# HeroRobot.net
KiCad netlist of a schematic drawn in Altium Designer
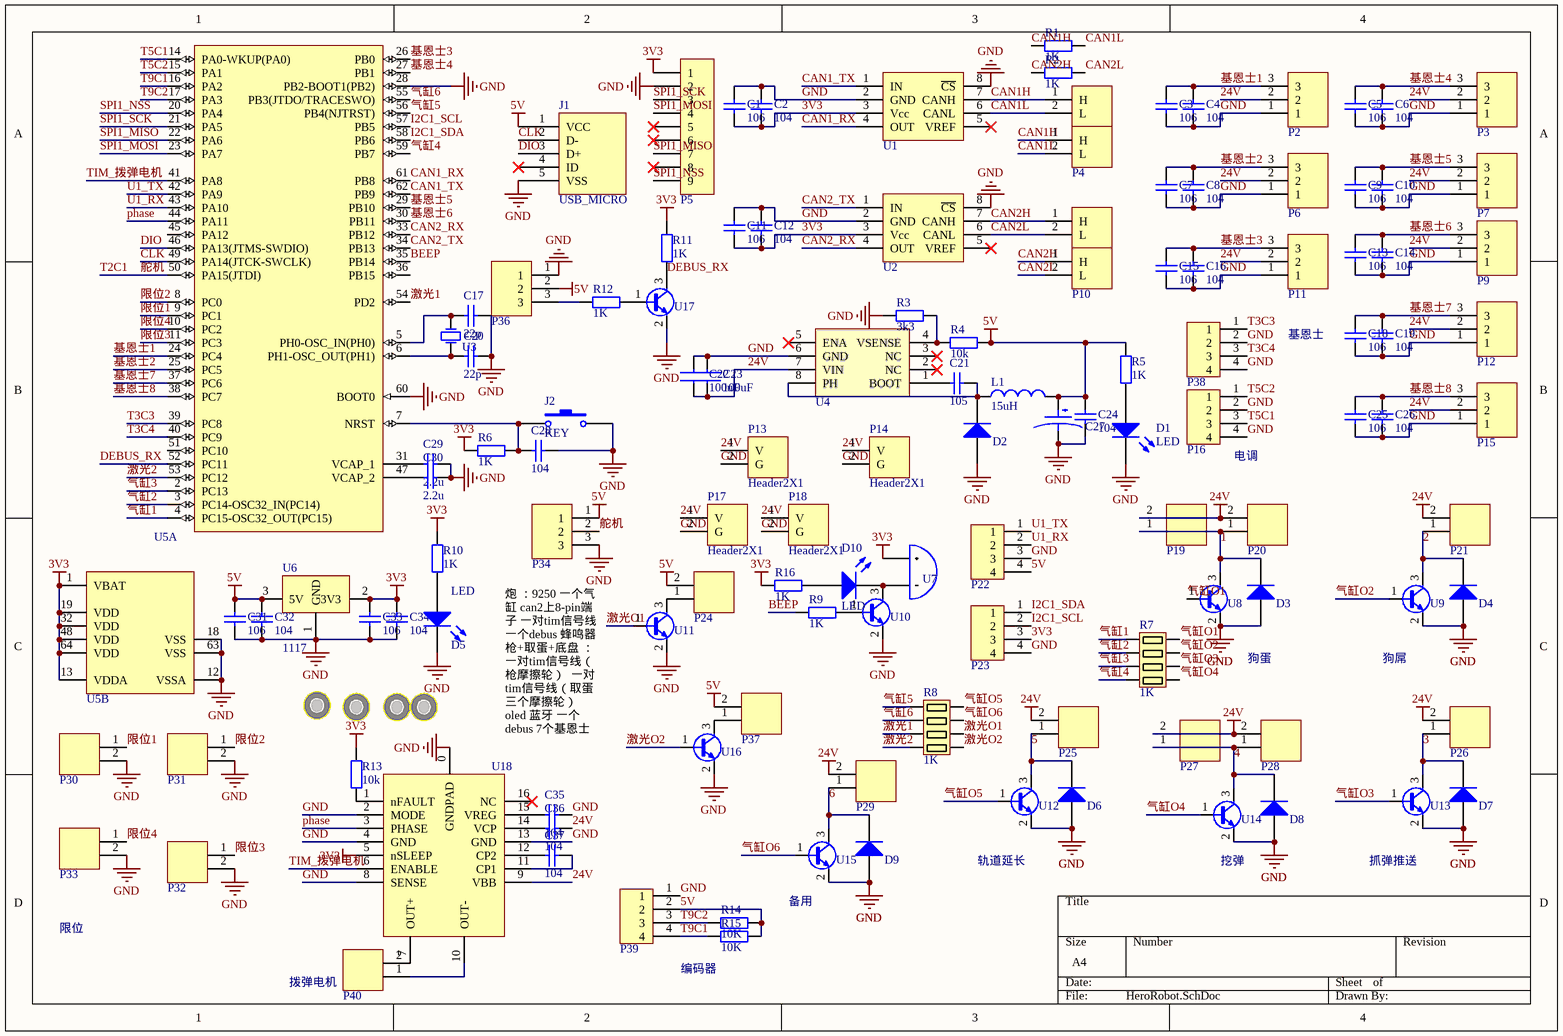
[diagram p0: HeroRobot.SchDoc]

(export (version "E")
  (design (tool "Eeschema 10.0.6"))
  (components
    (comp (ref "1") (value "Via_M3") (footprint "Via_M3") (libsource (lib "SHAWN") (part "Via_M3")))
    (comp (ref "2") (value "Via_M3") (footprint "Via_M3") (libsource (lib "SHAWN") (part "Via_M3")))
    (comp (ref "3") (value "Via_M3") (footprint "Via_M3") (libsource (lib "SHAWN") (part "Via_M3")))
    (comp (ref "4") (value "Via_M3") (footprint "Via_M3") (libsource (lib "SHAWN") (part "Via_M3")))
    (comp (ref "C1")
      (value "106")
      (footprint "0603C")
      (description "0603/0805")
      (libsource (lib "SHAWN") (part "C_106"))
    )
    (comp (ref "C2")
      (value "104")
      (footprint "0603C")
      (description "0603/0805")
      (libsource (lib "SHAWN") (part "C_104"))
    )
    (comp (ref "C3")
      (value "106")
      (footprint "0603C")
      (description "0603/0805")
      (libsource (lib "SHAWN") (part "C_106"))
    )
    (comp (ref "C4")
      (value "104")
      (footprint "0603C")
      (description "0603/0805")
      (libsource (lib "SHAWN") (part "C_104"))
    )
    (comp (ref "C5")
      (value "106")
      (footprint "0603C")
      (description "0603/0805")
      (libsource (lib "SHAWN") (part "C_106"))
    )
    (comp (ref "C6")
      (value "104")
      (footprint "0603C")
      (description "0603/0805")
      (libsource (lib "SHAWN") (part "C_104"))
    )
    (comp (ref "C7")
      (value "106")
      (footprint "0603C")
      (description "0603/0805")
      (libsource (lib "SHAWN") (part "C_106"))
    )
    (comp (ref "C8")
      (value "104")
      (footprint "0603C")
      (description "0603/0805")
      (libsource (lib "SHAWN") (part "C_104"))
    )
    (comp (ref "C9")
      (value "106")
      (footprint "0603C")
      (description "0603/0805")
      (libsource (lib "SHAWN") (part "C_106"))
    )
    (comp (ref "C10")
      (value "104")
      (footprint "0603C")
      (description "0603/0805")
      (libsource (lib "SHAWN") (part "C_104"))
    )
    (comp (ref "C11")
      (value "106")
      (footprint "0603C")
      (description "0603/0805")
      (libsource (lib "SHAWN") (part "C_106"))
    )
    (comp (ref "C12")
      (value "104")
      (footprint "0603C")
      (description "0603/0805")
      (libsource (lib "SHAWN") (part "C_104"))
    )
    (comp (ref "C13")
      (value "106")
      (footprint "0603C")
      (description "0603/0805")
      (libsource (lib "SHAWN") (part "C_106"))
    )
    (comp (ref "C14")
      (value "104")
      (footprint "0603C")
      (description "0603/0805")
      (libsource (lib "SHAWN") (part "C_104"))
    )
    (comp (ref "C15")
      (value "106")
      (footprint "0603C")
      (description "0603/0805")
      (libsource (lib "SHAWN") (part "C_106"))
    )
    (comp (ref "C16")
      (value "104")
      (footprint "0603C")
      (description "0603/0805")
      (libsource (lib "SHAWN") (part "C_104"))
    )
    (comp (ref "C17")
      (value "22p")
      (footprint "0603C")
      (description "0603/0805")
      (libsource (lib "SHAWN") (part "C_104"))
    )
    (comp (ref "C18")
      (value "106")
      (footprint "0603C")
      (description "0603/0805")
      (libsource (lib "SHAWN") (part "C_106"))
    )
    (comp (ref "C19")
      (value "104")
      (footprint "0603C")
      (description "0603/0805")
      (libsource (lib "SHAWN") (part "C_104"))
    )
    (comp (ref "C20")
      (value "22p")
      (footprint "0603C")
      (description "0603/0805")
      (libsource (lib "SHAWN") (part "C_104"))
    )
    (comp (ref "C21")
      (value "105")
      (footprint "0603C")
      (description "0603/0805")
      (libsource (lib "SHAWN") (part "C_106"))
    )
    (comp (ref "C22") (value "100uF") (footprint "1201C") (libsource (lib "SHAWN") (part "CAP100uF")))
    (comp (ref "C23") (value "100uF") (footprint "1201C") (libsource (lib "SHAWN") (part "CAP100uF")))
    (comp (ref "C24")
      (value "104")
      (footprint "0603C")
      (description "0603/0805")
      (libsource (lib "SHAWN") (part "C_104"))
    )
    (comp (ref "C25")
      (value "106")
      (footprint "0603C")
      (description "0603/0805")
      (libsource (lib "SHAWN") (part "C_106"))
    )
    (comp (ref "C26")
      (value "104")
      (footprint "0603C")
      (description "0603/0805")
      (libsource (lib "SHAWN") (part "C_104"))
    )
    (comp (ref "C27")
      (value "CAP_钽220")
      (footprint "cap_钽E封装")
      (description "CAP")
      (libsource (lib "SHAWN") (part "CAP_钽220"))
    )
    (comp (ref "C28")
      (value "104")
      (footprint "0603C")
      (description "0603/0805")
      (libsource (lib "SHAWN") (part "C_104"))
    )
    (comp (ref "C29")
      (value "2.2u")
      (footprint "0603C")
      (description "0603/0805")
      (libsource (lib "SHAWN") (part "C_104"))
    )
    (comp (ref "C30")
      (value "2.2u")
      (footprint "0603C")
      (description "0603/0805")
      (libsource (lib "SHAWN") (part "C_104"))
    )
    (comp (ref "C31")
      (value "106")
      (footprint "0603C")
      (description "0603/0805")
      (libsource (lib "SHAWN") (part "C_106"))
    )
    (comp (ref "C32")
      (value "104")
      (footprint "0603C")
      (description "0603/0805")
      (libsource (lib "SHAWN") (part "C_104"))
    )
    (comp (ref "C33")
      (value "106")
      (footprint "0603C")
      (description "0603/0805")
      (libsource (lib "SHAWN") (part "C_106"))
    )
    (comp (ref "C34")
      (value "104")
      (footprint "0603C")
      (description "0603/0805")
      (libsource (lib "SHAWN") (part "C_104"))
    )
    (comp (ref "C35")
      (value "104")
      (footprint "0603C")
      (description "0603/0805")
      (libsource (lib "SHAWN") (part "C_104"))
    )
    (comp (ref "C36")
      (value "104")
      (footprint "0603C")
      (description "0603/0805")
      (libsource (lib "SHAWN") (part "C_104"))
    )
    (comp (ref "C37")
      (value "104")
      (footprint "0603C")
      (description "0603/0805")
      (libsource (lib "SHAWN") (part "C_104"))
    )
    (comp (ref "D1") (value "LED") (footprint "LED_0603") (libsource (lib "SHAWN") (part "LED")))
    (comp (ref "D2")
      (value "Diode_SS34")
      (footprint "Diode_SS34")
      (description "肖特基二极管")
      (libsource (lib "SHAWN") (part "Diode_SS34"))
    )
    (comp (ref "D3")
      (value "Diode_SS34")
      (footprint "Diode_SS34")
      (description "肖特基二极管")
      (libsource (lib "SHAWN") (part "Diode_SS34"))
    )
    (comp (ref "D4")
      (value "Diode_SS34")
      (footprint "Diode_SS34")
      (description "肖特基二极管")
      (libsource (lib "SHAWN") (part "Diode_SS34"))
    )
    (comp (ref "D5") (value "LED") (footprint "LED_0603") (libsource (lib "SHAWN") (part "LED")))
    (comp (ref "D6")
      (value "Diode_SS34")
      (footprint "Diode_SS34")
      (description "肖特基二极管")
      (libsource (lib "SHAWN") (part "Diode_SS34"))
    )
    (comp (ref "D7")
      (value "Diode_SS34")
      (footprint "Diode_SS34")
      (description "肖特基二极管")
      (libsource (lib "SHAWN") (part "Diode_SS34"))
    )
    (comp (ref "D8")
      (value "Diode_SS34")
      (footprint "Diode_SS34")
      (description "肖特基二极管")
      (libsource (lib "SHAWN") (part "Diode_SS34"))
    )
    (comp (ref "D9")
      (value "Diode_SS34")
      (footprint "Diode_SS34")
      (description "肖特基二极管")
      (libsource (lib "SHAWN") (part "Diode_SS34"))
    )
    (comp (ref "D10") (value "LED") (footprint "LED_0603") (libsource (lib "SHAWN") (part "LED")))
    (comp (ref "J1") (value "USB_MICRO") (footprint "USB_MICRO") (libsource (lib "SHAWN") (part "USB_MICRO")))
    (comp (ref "J2") (value "KEY") (footprint "KEY") (libsource (lib "SHAWN") (part "KEY")))
    (comp (ref "L1")
      (value "15uH")
      (footprint "Inductor7.2X7.2")
      (description "屏蔽电感")
      (libsource (lib "SHAWN") (part "Inductor"))
    )
    (comp (ref "P1")
      (value "Header_CAN")
      (footprint "Header2_3002")
      (libsource (lib "SHAWN") (part "Header_CAN"))
    )
    (comp (ref "P2") (value "Header3") (footprint "Header3_white") (libsource (lib "SHAWN") (part "Header3")))
    (comp (ref "P3") (value "Header3") (footprint "Header3_white") (libsource (lib "SHAWN") (part "Header3")))
    (comp (ref "P4")
      (value "Header_CAN")
      (footprint "Header2_3002")
      (libsource (lib "SHAWN") (part "Header_CAN"))
    )
    (comp (ref "P5") (value "Header9") (footprint "Header9") (libsource (lib "SHAWN") (part "Header9")))
    (comp (ref "P6") (value "Header3") (footprint "Header3_white") (libsource (lib "SHAWN") (part "Header3")))
    (comp (ref "P7") (value "Header3") (footprint "Header3_white") (libsource (lib "SHAWN") (part "Header3")))
    (comp (ref "P8")
      (value "Header_CAN")
      (footprint "Header2_3002")
      (libsource (lib "SHAWN") (part "Header_CAN"))
    )
    (comp (ref "P9") (value "Header3") (footprint "Header3_white") (libsource (lib "SHAWN") (part "Header3")))
    (comp (ref "P10")
      (value "Header_CAN")
      (footprint "Header2_3002")
      (libsource (lib "SHAWN") (part "Header_CAN"))
    )
    (comp (ref "P11")
      (value "Header3")
      (footprint "Header3_white")
      (libsource (lib "SHAWN") (part "Header3"))
    )
    (comp (ref "P12")
      (value "Header3")
      (footprint "Header3_white")
      (libsource (lib "SHAWN") (part "Header3"))
    )
    (comp (ref "P13")
      (value "Header2X1")
      (footprint "Header_POWER")
      (description "power")
      (libsource (lib "SHAWN") (part "Header2X1"))
    )
    (comp (ref "P14")
      (value "Header2X1")
      (footprint "Header_POWER")
      (description "power")
      (libsource (lib "SHAWN") (part "Header2X1"))
    )
    (comp (ref "P15")
      (value "Header3")
      (footprint "Header3_white")
      (libsource (lib "SHAWN") (part "Header3"))
    )
    (comp (ref "P16")
      (value "Header4")
      (footprint "Header4_white")
      (libsource (lib "SHAWN") (part "Header4"))
    )
    (comp (ref "P17")
      (value "Header2X1")
      (footprint "Header_POWER")
      (description "power")
      (libsource (lib "SHAWN") (part "Header2X1"))
    )
    (comp (ref "P18")
      (value "Header2X1")
      (footprint "Header_POWER")
      (description "power")
      (libsource (lib "SHAWN") (part "Header2X1"))
    )
    (comp (ref "P19") (value "Header") (footprint "Header2_white") (libsource (lib "SHAWN") (part "Header2")))
    (comp (ref "P20") (value "Header") (footprint "Header2_white") (libsource (lib "SHAWN") (part "Header2")))
    (comp (ref "P21") (value "Header") (footprint "Header2_white") (libsource (lib "SHAWN") (part "Header2")))
    (comp (ref "P22") (value "Header4") (footprint "Header4") (libsource (lib "SHAWN") (part "Header4")))
    (comp (ref "P23") (value "Header4") (footprint "Header4") (libsource (lib "SHAWN") (part "Header4")))
    (comp (ref "P24") (value "Header") (footprint "Header2_white") (libsource (lib "SHAWN") (part "Header2")))
    (comp (ref "P25") (value "Header") (footprint "Header2_white") (libsource (lib "SHAWN") (part "Header2")))
    (comp (ref "P26") (value "Header") (footprint "Header2_white") (libsource (lib "SHAWN") (part "Header2")))
    (comp (ref "P27") (value "Header") (footprint "Header2_white") (libsource (lib "SHAWN") (part "Header2")))
    (comp (ref "P28") (value "Header") (footprint "Header2_white") (libsource (lib "SHAWN") (part "Header2")))
    (comp (ref "P29") (value "Header") (footprint "Header2_white") (libsource (lib "SHAWN") (part "Header2")))
    (comp (ref "P30") (value "Header") (footprint "Header2_white") (libsource (lib "") (part "Header2_2")))
    (comp (ref "P31") (value "Header") (footprint "Header2_white") (libsource (lib "") (part "Header2_2")))
    (comp (ref "P32") (value "Header") (footprint "Header2_white") (libsource (lib "") (part "Header2_2")))
    (comp (ref "P33") (value "Header") (footprint "Header2_white") (libsource (lib "") (part "Header2_2")))
    (comp (ref "P34") (value "Header3") (footprint "Header3_white") (libsource (lib "") (part "Header3_1")))
    (comp (ref "P36") (value "Header3") (footprint "Header3_white") (libsource (lib "") (part "Header3_1")))
    (comp (ref "P37") (value "Header") (footprint "Header2_white") (libsource (lib "SHAWN") (part "Header2")))
    (comp (ref "P38")
      (value "Header4")
      (footprint "Header4_white")
      (libsource (lib "SHAWN") (part "Header4"))
    )
    (comp (ref "P39")
      (value "Header4")
      (footprint "Header4_white")
      (libsource (lib "SHAWN") (part "Header4"))
    )
    (comp (ref "P40") (value "Header") (footprint "Header2_white") (libsource (lib "") (part "Header2_1")))
    (comp (ref "R1")
      (value "1K")
      (footprint "0603R")
      (description "0603/0805")
      (libsource (lib "SHAWN") (part "R"))
    )
    (comp (ref "R2")
      (value "1K")
      (footprint "0603R")
      (description "0603/0805")
      (libsource (lib "SHAWN") (part "R"))
    )
    (comp (ref "R3")
      (value "3k3")
      (footprint "0603R")
      (description "0603/0805")
      (libsource (lib "") (part "R_2"))
    )
    (comp (ref "R4")
      (value "10k")
      (footprint "0603R")
      (description "0603/0805")
      (libsource (lib "") (part "R_2"))
    )
    (comp (ref "R5")
      (value "1K")
      (footprint "0603R")
      (description "0603/0805")
      (libsource (lib "") (part "R_1"))
    )
    (comp (ref "R6")
      (value "1K")
      (footprint "0603R")
      (description "0603/0805")
      (libsource (lib "") (part "R_2"))
    )
    (comp (ref "R7") (value "1K") (footprint "8P4R_0603") (libsource (lib "SHAWN") (part "R_8P4R")))
    (comp (ref "R8") (value "1K") (footprint "8P4R_0603") (libsource (lib "SHAWN") (part "R_8P4R")))
    (comp (ref "R9")
      (value "1K")
      (footprint "0603R")
      (description "0603/0805")
      (libsource (lib "") (part "R_2"))
    )
    (comp (ref "R10")
      (value "1K")
      (footprint "0603R")
      (description "0603/0805")
      (libsource (lib "") (part "R_1"))
    )
    (comp (ref "R11")
      (value "1K")
      (footprint "0603R")
      (description "0603/0805")
      (libsource (lib "") (part "R_1"))
    )
    (comp (ref "R12")
      (value "1K")
      (footprint "0603R")
      (description "0603/0805")
      (libsource (lib "") (part "R_2"))
    )
    (comp (ref "R13")
      (value "10k")
      (footprint "0603R")
      (description "0603/0805")
      (libsource (lib "") (part "R_1"))
    )
    (comp (ref "R14")
      (value "10K")
      (footprint "0603R")
      (description "0603/0805")
      (libsource (lib "SHAWN") (part "R"))
    )
    (comp (ref "R15")
      (value "10K")
      (footprint "0603R")
      (description "0603/0805")
      (libsource (lib "SHAWN") (part "R"))
    )
    (comp (ref "R16")
      (value "1K")
      (footprint "0603R")
      (description "0603/0805")
      (libsource (lib "SHAWN") (part "R"))
    )
    (comp (ref "U1")
      (value "VD230")
      (footprint "SO_8")
      (description "SO-8")
      (libsource (lib "SHAWN") (part "VD230"))
    )
    (comp (ref "U2")
      (value "VD230")
      (footprint "SO_8")
      (description "SO-8")
      (libsource (lib "SHAWN") (part "VD230"))
    )
    (comp (ref "U3") (value "XTAL") (footprint "XATL_8M") (libsource (lib "SHAWN") (part "XTAL")))
    (comp (ref "U4")
      (value "TPS5430/5450")
      (footprint "TPS5430")
      (description "降压")
      (libsource (lib "SHAWN") (part "TPS5430/5450"))
    )
    (comp (ref "U5")
      (value "STM32F405RGT6(F103RCT6)")
      (footprint "LQFP_64Pins - duplicate")
      (description "64PINS")
      (libsource (lib "SHAWN") (part "STM32F405RGT6(F103RCT6)"))
    )
    (comp (ref "U6") (value "1117") (footprint "SOT-223") (libsource (lib "SHAWN") (part "AMS1117-3.3")))
    (comp (ref "U7") (value "Bell") (footprint "BELL_无源") (libsource (lib "SHAWN") (part "Bell")))
    (comp (ref "U8") (value "BJT-2N5551") (footprint "SOT_23") (libsource (lib "SHAWN") (part "BJT-2N5551")))
    (comp (ref "U9") (value "BJT-2N5551") (footprint "SOT_23") (libsource (lib "SHAWN") (part "BJT-2N5551")))
    (comp (ref "U10") (value "BJT-2N5551") (footprint "SOT_23") (libsource (lib "SHAWN") (part "BJT-2N5551")))
    (comp (ref "U11") (value "BJT-2N5551") (footprint "SOT_23") (libsource (lib "SHAWN") (part "BJT-2N5551")))
    (comp (ref "U12") (value "BJT-2N5551") (footprint "SOT_23") (libsource (lib "SHAWN") (part "BJT-2N5551")))
    (comp (ref "U13") (value "BJT-2N5551") (footprint "SOT_23") (libsource (lib "SHAWN") (part "BJT-2N5551")))
    (comp (ref "U14") (value "BJT-2N5551") (footprint "SOT_23") (libsource (lib "SHAWN") (part "BJT-2N5551")))
    (comp (ref "U15") (value "BJT-2N5551") (footprint "SOT_23") (libsource (lib "SHAWN") (part "BJT-2N5551")))
    (comp (ref "U16") (value "BJT-2N5551") (footprint "SOT_23") (libsource (lib "SHAWN") (part "BJT-2N5551")))
    (comp (ref "U17") (value "BJT-2N5551") (footprint "SOT_23") (libsource (lib "SHAWN") (part "BJT-2N5551")))
    (comp (ref "U18")
      (value "DRV8800")
      (footprint "HTSSOP")
      (description "HTSSOP")
      (libsource (lib "SHAWN") (part "DRV8800"))
    )
  )
  (nets
    (net (code "1") (name "/1") (class "Default")
      (node (ref "D3") (pin "2") (pinfunction "K_2") (pintype "passive"))
      (node (ref "P19") (pin "1") (pinfunction "1_1") (pintype "passive"))
      (node (ref "P20") (pin "1") (pinfunction "1_1") (pintype "passive"))
      (node (ref "U8") (pin "3") (pinfunction "c_3") (pintype "passive"))
    )
    (net (code "2") (name "/2") (class "Default")
      (node (ref "D4") (pin "2") (pinfunction "K_2") (pintype "passive"))
      (node (ref "P21") (pin "1") (pinfunction "1_1") (pintype "passive"))
      (node (ref "U9") (pin "3") (pinfunction "c_3") (pintype "passive"))
    )
    (net (code "3") (name "/3") (class "Default")
      (node (ref "D7") (pin "2") (pinfunction "K_2") (pintype "passive"))
      (node (ref "P26") (pin "1") (pinfunction "1_1") (pintype "passive"))
      (node (ref "U13") (pin "3") (pinfunction "c_3") (pintype "passive"))
    )
    (net (code "4") (name "/4") (class "Default")
      (node (ref "D8") (pin "2") (pinfunction "K_2") (pintype "passive"))
      (node (ref "P27") (pin "1") (pinfunction "1_1") (pintype "passive"))
      (node (ref "P28") (pin "1") (pinfunction "1_1") (pintype "passive"))
      (node (ref "U14") (pin "3") (pinfunction "c_3") (pintype "passive"))
    )
    (net (code "5") (name "/5") (class "Default")
      (node (ref "D6") (pin "2") (pinfunction "K_2") (pintype "passive"))
      (node (ref "P25") (pin "1") (pinfunction "1_1") (pintype "passive"))
      (node (ref "U12") (pin "3") (pinfunction "c_3") (pintype "passive"))
    )
    (net (code "6") (name "/6") (class "Default")
      (node (ref "D9") (pin "2") (pinfunction "K_2") (pintype "passive"))
      (node (ref "P29") (pin "1") (pinfunction "1_1") (pintype "passive"))
      (node (ref "U15") (pin "3") (pinfunction "c_3") (pintype "passive"))
    )
    (net (code "7") (name "/BEEP") (class "Default")
      (node (ref "R9") (pin "2") (pinfunction "2_2") (pintype "passive"))
      (node (ref "U5") (pin "35") (pinfunction "PB14_35") (pintype "bidirectional"))
    )
    (net (code "8") (name "/CAN1H") (class "Default")
      (node (ref "P1") (pin "1") (pinfunction "H_1") (pintype "passive"))
      (node (ref "P4") (pin "1") (pinfunction "H_1") (pintype "passive"))
      (node (ref "R1") (pin "1") (pinfunction "1_1") (pintype "passive"))
      (node (ref "U1") (pin "7") (pinfunction "CANH_7") (pintype "passive"))
    )
    (net (code "9") (name "/CAN1L") (class "Default")
      (node (ref "P1") (pin "2") (pinfunction "L_2") (pintype "passive"))
      (node (ref "P4") (pin "2") (pinfunction "L_2") (pintype "passive"))
      (node (ref "R1") (pin "2") (pinfunction "2_2") (pintype "passive"))
      (node (ref "U1") (pin "6") (pinfunction "CANL_6") (pintype "passive"))
    )
    (net (code "10") (name "/CAN1_RX") (class "Default")
      (node (ref "U1") (pin "4") (pinfunction "OUT_4") (pintype "passive"))
      (node (ref "U5") (pin "61") (pinfunction "PB8_61") (pintype "bidirectional"))
    )
    (net (code "11") (name "/CAN1_TX") (class "Default")
      (node (ref "U1") (pin "1") (pinfunction "IN_1") (pintype "passive"))
      (node (ref "U5") (pin "62") (pinfunction "PB9_62") (pintype "bidirectional"))
    )
    (net (code "12") (name "/CAN2H") (class "Default")
      (node (ref "P10") (pin "1") (pinfunction "H_1") (pintype "passive"))
      (node (ref "P8") (pin "1") (pinfunction "H_1") (pintype "passive"))
      (node (ref "R2") (pin "1") (pinfunction "1_1") (pintype "passive"))
      (node (ref "U2") (pin "7") (pinfunction "CANH_7") (pintype "passive"))
    )
    (net (code "13") (name "/CAN2L") (class "Default")
      (node (ref "P10") (pin "2") (pinfunction "L_2") (pintype "passive"))
      (node (ref "P8") (pin "2") (pinfunction "L_2") (pintype "passive"))
      (node (ref "R2") (pin "2") (pinfunction "2_2") (pintype "passive"))
      (node (ref "U2") (pin "6") (pinfunction "CANL_6") (pintype "passive"))
    )
    (net (code "14") (name "/CAN2_RX") (class "Default")
      (node (ref "U2") (pin "4") (pinfunction "OUT_4") (pintype "passive"))
      (node (ref "U5") (pin "33") (pinfunction "PB12_33") (pintype "bidirectional"))
    )
    (net (code "15") (name "/CAN2_TX") (class "Default")
      (node (ref "U2") (pin "1") (pinfunction "IN_1") (pintype "passive"))
      (node (ref "U5") (pin "34") (pinfunction "PB13_34") (pintype "bidirectional"))
    )
    (net (code "16") (name "/CLK") (class "Default")
      (node (ref "J1") (pin "2") (pinfunction "D-_2") (pintype "passive"))
      (node (ref "U5") (pin "49") (pinfunction "PA14(JTCK-SWCLK)_49") (pintype "bidirectional"))
    )
    (net (code "17") (name "/DEBUS_RX") (class "Default")
      (node (ref "R11") (pin "1") (pinfunction "1_1") (pintype "passive"))
      (node (ref "U17") (pin "3") (pinfunction "c_3") (pintype "passive"))
      (node (ref "U5") (pin "52") (pinfunction "PC11_52") (pintype "bidirectional"))
    )
    (net (code "18") (name "/DIO") (class "Default")
      (node (ref "J1") (pin "3") (pinfunction "D+_3") (pintype "passive"))
      (node (ref "U5") (pin "46") (pinfunction "PA13(JTMS-SWDIO)_46") (pintype "bidirectional"))
    )
    (net (code "19") (name "/I2C1_SCL") (class "Default")
      (node (ref "P23") (pin "2") (pinfunction "2_2") (pintype "passive"))
      (node (ref "U5") (pin "57") (pinfunction "PB5_57") (pintype "bidirectional"))
    )
    (net (code "20") (name "/I2C1_SDA") (class "Default")
      (node (ref "P23") (pin "1") (pinfunction "1_1") (pintype "passive"))
      (node (ref "U5") (pin "58") (pinfunction "PB6_58") (pintype "bidirectional"))
    )
    (net (code "21") (name "/SPI1_MISO") (class "Default")
      (node (ref "P5") (pin "7") (pinfunction "7_7") (pintype "passive"))
      (node (ref "U5") (pin "22") (pinfunction "PA6_22") (pintype "bidirectional"))
    )
    (net (code "22") (name "/SPI1_MOSI") (class "Default")
      (node (ref "P5") (pin "4") (pinfunction "4_4") (pintype "passive"))
      (node (ref "U5") (pin "23") (pinfunction "PA7_23") (pintype "bidirectional"))
    )
    (net (code "23") (name "/SPI1_NSS") (class "Default")
      (node (ref "P5") (pin "9") (pinfunction "9_9") (pintype "passive"))
      (node (ref "U5") (pin "20") (pinfunction "PA4_20") (pintype "bidirectional"))
    )
    (net (code "24") (name "/SPI1_SCK") (class "Default")
      (node (ref "P5") (pin "3") (pinfunction "3_3") (pintype "passive"))
      (node (ref "U5") (pin "21") (pinfunction "PA5_21") (pintype "bidirectional"))
    )
    (net (code "25") (name "/T2C1") (class "Default")
      (node (ref "P34") (pin "2") (pinfunction "2_2") (pintype "passive"))
      (node (ref "U5") (pin "50") (pinfunction "PA15(JTDI)_50") (pintype "bidirectional"))
    )
    (net (code "26") (name "/T3C3") (class "Default")
      (node (ref "P38") (pin "1") (pinfunction "1_1") (pintype "passive"))
      (node (ref "U5") (pin "39") (pinfunction "PC8_39") (pintype "bidirectional"))
    )
    (net (code "27") (name "/T3C4") (class "Default")
      (node (ref "P38") (pin "3") (pinfunction "3_3") (pintype "passive"))
      (node (ref "U5") (pin "40") (pinfunction "PC9_40") (pintype "bidirectional"))
    )
    (net (code "28") (name "/T5C1") (class "Default")
      (node (ref "P16") (pin "3") (pinfunction "3_3") (pintype "passive"))
      (node (ref "U5") (pin "14") (pinfunction "PA0-WKUP(PA0)_14") (pintype "bidirectional"))
    )
    (net (code "29") (name "/T5C2") (class "Default")
      (node (ref "P16") (pin "1") (pinfunction "1_1") (pintype "passive"))
      (node (ref "U5") (pin "15") (pinfunction "PA1_15") (pintype "bidirectional"))
    )
    (net (code "30") (name "/T9C1") (class "Default")
      (node (ref "P39") (pin "4") (pinfunction "4_4") (pintype "passive"))
      (node (ref "R15") (pin "1") (pinfunction "1_1") (pintype "passive"))
      (node (ref "U5") (pin "16") (pinfunction "PA2_16") (pintype "bidirectional"))
    )
    (net (code "31") (name "/T9C2") (class "Default")
      (node (ref "P39") (pin "3") (pinfunction "3_3") (pintype "passive"))
      (node (ref "R14") (pin "1") (pinfunction "1_1") (pintype "passive"))
      (node (ref "U5") (pin "17") (pinfunction "PA3_17") (pintype "bidirectional"))
    )
    (net (code "32") (name "/TIM_拨弹电机") (class "Default")
      (node (ref "U18") (pin "6") (pinfunction "ENABLE_6") (pintype "passive"))
      (node (ref "U5") (pin "41") (pinfunction "PA8_41") (pintype "bidirectional"))
    )
    (net (code "33") (name "/U1_RX") (class "Default")
      (node (ref "P22") (pin "2") (pinfunction "2_2") (pintype "passive"))
      (node (ref "U5") (pin "43") (pinfunction "PA10_43") (pintype "bidirectional"))
    )
    (net (code "34") (name "/U1_TX") (class "Default")
      (node (ref "P22") (pin "1") (pinfunction "1_1") (pintype "passive"))
      (node (ref "U5") (pin "42") (pinfunction "PA9_42") (pintype "bidirectional"))
    )
    (net (code "35") (name "/phase") (class "Default")
      (node (ref "U18") (pin "3") (pinfunction "PHASE_3") (pintype "passive"))
      (node (ref "U5") (pin "44") (pinfunction "PA11_44") (pintype "bidirectional"))
    )
    (net (code "36") (name "/基恩士1") (class "Default")
      (node (ref "C3") (pin "2") (pinfunction "2_2") (pintype "passive"))
      (node (ref "C4") (pin "2") (pinfunction "2_2") (pintype "passive"))
      (node (ref "P2") (pin "3") (pinfunction "3_3") (pintype "passive"))
      (node (ref "U5") (pin "24") (pinfunction "PC4_24") (pintype "bidirectional"))
    )
    (net (code "37") (name "/基恩士2") (class "Default")
      (node (ref "C7") (pin "2") (pinfunction "2_2") (pintype "passive"))
      (node (ref "C8") (pin "2") (pinfunction "2_2") (pintype "passive"))
      (node (ref "P6") (pin "3") (pinfunction "3_3") (pintype "passive"))
      (node (ref "U5") (pin "25") (pinfunction "PC5_25") (pintype "bidirectional"))
    )
    (net (code "38") (name "/基恩士3") (class "Default")
      (node (ref "C15") (pin "2") (pinfunction "2_2") (pintype "passive"))
      (node (ref "C16") (pin "2") (pinfunction "2_2") (pintype "passive"))
      (node (ref "P11") (pin "3") (pinfunction "3_3") (pintype "passive"))
      (node (ref "U5") (pin "26") (pinfunction "PB0_26") (pintype "bidirectional"))
    )
    (net (code "39") (name "/基恩士4") (class "Default")
      (node (ref "C5") (pin "2") (pinfunction "2_2") (pintype "passive"))
      (node (ref "C6") (pin "2") (pinfunction "2_2") (pintype "passive"))
      (node (ref "P3") (pin "3") (pinfunction "3_3") (pintype "passive"))
      (node (ref "U5") (pin "27") (pinfunction "PB1_27") (pintype "bidirectional"))
    )
    (net (code "40") (name "/基恩士5") (class "Default")
      (node (ref "C10") (pin "2") (pinfunction "2_2") (pintype "passive"))
      (node (ref "C9") (pin "2") (pinfunction "2_2") (pintype "passive"))
      (node (ref "P7") (pin "3") (pinfunction "3_3") (pintype "passive"))
      (node (ref "U5") (pin "29") (pinfunction "PB10_29") (pintype "bidirectional"))
    )
    (net (code "41") (name "/基恩士6") (class "Default")
      (node (ref "C13") (pin "2") (pinfunction "2_2") (pintype "passive"))
      (node (ref "C14") (pin "2") (pinfunction "2_2") (pintype "passive"))
      (node (ref "P9") (pin "3") (pinfunction "3_3") (pintype "passive"))
      (node (ref "U5") (pin "30") (pinfunction "PB11_30") (pintype "bidirectional"))
    )
    (net (code "42") (name "/基恩士7") (class "Default")
      (node (ref "C18") (pin "2") (pinfunction "2_2") (pintype "passive"))
      (node (ref "C19") (pin "2") (pinfunction "2_2") (pintype "passive"))
      (node (ref "P12") (pin "3") (pinfunction "3_3") (pintype "passive"))
      (node (ref "U5") (pin "37") (pinfunction "PC6_37") (pintype "bidirectional"))
    )
    (net (code "43") (name "/基恩士8") (class "Default")
      (node (ref "C25") (pin "2") (pinfunction "2_2") (pintype "passive"))
      (node (ref "C26") (pin "2") (pinfunction "2_2") (pintype "passive"))
      (node (ref "P15") (pin "3") (pinfunction "3_3") (pintype "passive"))
      (node (ref "U5") (pin "38") (pinfunction "PC7_38") (pintype "bidirectional"))
    )
    (net (code "44") (name "/气缸1") (class "Default")
      (node (ref "R7") (pin "1") (pinfunction "1_1") (pintype "passive"))
      (node (ref "U5") (pin "4") (pinfunction "PC15-OSC32_OUT(PC15)_4") (pintype "bidirectional"))
    )
    (net (code "45") (name "/气缸2") (class "Default")
      (node (ref "R7") (pin "2") (pinfunction "2_2") (pintype "passive"))
      (node (ref "U5") (pin "3") (pinfunction "PC14-OSC32_IN(PC14)_3") (pintype "bidirectional"))
    )
    (net (code "46") (name "/气缸3") (class "Default")
      (node (ref "R7") (pin "3") (pinfunction "3_3") (pintype "passive"))
      (node (ref "U5") (pin "2") (pinfunction "PC13_2") (pintype "bidirectional"))
    )
    (net (code "47") (name "/气缸4") (class "Default")
      (node (ref "R7") (pin "4") (pinfunction "4_4") (pintype "passive"))
      (node (ref "U5") (pin "59") (pinfunction "PB7_59") (pintype "bidirectional"))
    )
    (net (code "48") (name "/气缸5") (class "Default")
      (node (ref "R8") (pin "1") (pinfunction "1_1") (pintype "passive"))
      (node (ref "U5") (pin "56") (pinfunction "PB4(NJTRST)_56") (pintype "bidirectional"))
    )
    (net (code "49") (name "/气缸6") (class "Default")
      (node (ref "R8") (pin "2") (pinfunction "2_2") (pintype "passive"))
      (node (ref "U5") (pin "55") (pinfunction "PB3(JTDO/TRACESWO)_55") (pintype "bidirectional"))
    )
    (net (code "50") (name "/气缸O1") (class "Default")
      (node (ref "R7") (pin "8") (pinfunction "8_8") (pintype "passive"))
      (node (ref "U8") (pin "1") (pinfunction "e_1") (pintype "passive"))
    )
    (net (code "51") (name "/气缸O2") (class "Default")
      (node (ref "R7") (pin "7") (pinfunction "7_7") (pintype "passive"))
      (node (ref "U9") (pin "1") (pinfunction "e_1") (pintype "passive"))
    )
    (net (code "52") (name "/气缸O3") (class "Default")
      (node (ref "R7") (pin "6") (pinfunction "6_6") (pintype "passive"))
      (node (ref "U13") (pin "1") (pinfunction "e_1") (pintype "passive"))
    )
    (net (code "53") (name "/气缸O4") (class "Default")
      (node (ref "R7") (pin "5") (pinfunction "5_5") (pintype "passive"))
      (node (ref "U14") (pin "1") (pinfunction "e_1") (pintype "passive"))
    )
    (net (code "54") (name "/气缸O5") (class "Default")
      (node (ref "R8") (pin "8") (pinfunction "8_8") (pintype "passive"))
      (node (ref "U12") (pin "1") (pinfunction "e_1") (pintype "passive"))
    )
    (net (code "55") (name "/气缸O6") (class "Default")
      (node (ref "R8") (pin "7") (pinfunction "7_7") (pintype "passive"))
      (node (ref "U15") (pin "1") (pinfunction "e_1") (pintype "passive"))
    )
    (net (code "56") (name "/激光1") (class "Default")
      (node (ref "R8") (pin "3") (pinfunction "3_3") (pintype "passive"))
      (node (ref "U5") (pin "54") (pinfunction "PD2_54") (pintype "bidirectional"))
    )
    (net (code "57") (name "/激光2") (class "Default")
      (node (ref "R8") (pin "4") (pinfunction "4_4") (pintype "passive"))
      (node (ref "U5") (pin "53") (pinfunction "PC12_53") (pintype "bidirectional"))
    )
    (net (code "58") (name "/激光O1") (class "Default")
      (node (ref "R8") (pin "6") (pinfunction "6_6") (pintype "passive"))
      (node (ref "U11") (pin "1") (pinfunction "e_1") (pintype "passive"))
    )
    (net (code "59") (name "/激光O2") (class "Default")
      (node (ref "R8") (pin "5") (pinfunction "5_5") (pintype "passive"))
      (node (ref "U16") (pin "1") (pinfunction "e_1") (pintype "passive"))
    )
    (net (code "60") (name "/限位1") (class "Default")
      (node (ref "P30") (pin "1") (pinfunction "1_1") (pintype "passive"))
      (node (ref "U5") (pin "9") (pinfunction "PC1_9") (pintype "bidirectional"))
    )
    (net (code "61") (name "/限位2") (class "Default")
      (node (ref "P31") (pin "1") (pinfunction "1_1") (pintype "passive"))
      (node (ref "U5") (pin "8") (pinfunction "PC0_8") (pintype "bidirectional"))
    )
    (net (code "62") (name "/限位3") (class "Default")
      (node (ref "P32") (pin "1") (pinfunction "1_1") (pintype "passive"))
      (node (ref "U5") (pin "11") (pinfunction "PC3_11") (pintype "bidirectional"))
    )
    (net (code "63") (name "/限位4") (class "Default")
      (node (ref "P33") (pin "1") (pinfunction "1_1") (pintype "passive"))
      (node (ref "U5") (pin "10") (pinfunction "PC2_10") (pintype "bidirectional"))
    )
    (net (code "64") (name "3V3") (class "Default")
      (node (ref "C1") (pin "1") (pinfunction "1_1") (pintype "passive"))
      (node (ref "C11") (pin "1") (pinfunction "1_1") (pintype "passive"))
      (node (ref "C12") (pin "1") (pinfunction "1_1") (pintype "passive"))
      (node (ref "C2") (pin "1") (pinfunction "1_1") (pintype "passive"))
      (node (ref "C33") (pin "2") (pinfunction "2_2") (pintype "passive"))
      (node (ref "C34") (pin "2") (pinfunction "2_2") (pintype "passive"))
      (node (ref "P23") (pin "3") (pinfunction "3_3") (pintype "passive"))
      (node (ref "P5") (pin "1") (pinfunction "1_1") (pintype "passive"))
      (node (ref "R10") (pin "2") (pinfunction "2_2") (pintype "passive"))
      (node (ref "R11") (pin "2") (pinfunction "2_2") (pintype "passive"))
      (node (ref "R13") (pin "2") (pinfunction "2_2") (pintype "passive"))
      (node (ref "R16") (pin "1") (pinfunction "1_1") (pintype "passive"))
      (node (ref "R6") (pin "2") (pinfunction "2_2") (pintype "passive"))
      (node (ref "U1") (pin "3") (pinfunction "Vcc_3") (pintype "passive"))
      (node (ref "U18") (pin "5") (pinfunction "nSLEEP_5") (pintype "passive"))
      (node (ref "U2") (pin "3") (pinfunction "Vcc_3") (pintype "passive"))
      (node (ref "U5") (pin "1") (pinfunction "VBAT_1") (pintype "power_in"))
      (node (ref "U5") (pin "13") (pinfunction "VDDA_13") (pintype "power_in"))
      (node (ref "U5") (pin "19") (pinfunction "VDD_19") (pintype "power_in"))
      (node (ref "U5") (pin "32") (pinfunction "VDD_32") (pintype "power_in"))
      (node (ref "U5") (pin "48") (pinfunction "VDD_48") (pintype "power_in"))
      (node (ref "U5") (pin "64") (pinfunction "VDD_64") (pintype "power_in"))
      (node (ref "U6") (pin "2") (pinfunction "3V3_2") (pintype "passive"))
      (node (ref "U7") (pin "1") (pinfunction "A_1") (pintype "passive"))
    )
    (net (code "65") (name "5V") (class "Default")
      (node (ref "C24") (pin "2") (pinfunction "2_2") (pintype "passive"))
      (node (ref "C27") (pin "2") (pinfunction "2_2") (pintype "passive"))
      (node (ref "C31") (pin "2") (pinfunction "2_2") (pintype "passive"))
      (node (ref "C32") (pin "2") (pinfunction "2_2") (pintype "passive"))
      (node (ref "J1") (pin "1") (pinfunction "VCC_1") (pintype "passive"))
      (node (ref "L1") (pin "2") (pinfunction "2_2") (pintype "passive"))
      (node (ref "P22") (pin "4") (pinfunction "4_4") (pintype "passive"))
      (node (ref "P24") (pin "2") (pinfunction "2_2") (pintype "passive"))
      (node (ref "P34") (pin "1") (pinfunction "1_1") (pintype "passive"))
      (node (ref "P36") (pin "2") (pinfunction "2_2") (pintype "passive"))
      (node (ref "P37") (pin "2") (pinfunction "2_2") (pintype "passive"))
      (node (ref "P39") (pin "2") (pinfunction "2_2") (pintype "passive"))
      (node (ref "R14") (pin "2") (pinfunction "2_2") (pintype "passive"))
      (node (ref "R15") (pin "2") (pinfunction "2_2") (pintype "passive"))
      (node (ref "R4") (pin "1") (pinfunction "1_1") (pintype "passive"))
      (node (ref "R5") (pin "2") (pinfunction "2_2") (pintype "passive"))
      (node (ref "U6") (pin "3") (pinfunction "5V_3") (pintype "passive"))
    )
    (net (code "66") (name "24V") (class "Default")
      (node (ref "C22") (pin "1") (pinfunction "1_1") (pintype "passive"))
      (node (ref "C23") (pin "1") (pinfunction "1_1") (pintype "passive"))
      (node (ref "C36") (pin "2") (pinfunction "2_2") (pintype "passive"))
      (node (ref "P11") (pin "2") (pinfunction "2_2") (pintype "passive"))
      (node (ref "P12") (pin "2") (pinfunction "2_2") (pintype "passive"))
      (node (ref "P13") (pin "1") (pinfunction "V_1") (pintype "passive"))
      (node (ref "P14") (pin "1") (pinfunction "V_1") (pintype "passive"))
      (node (ref "P15") (pin "2") (pinfunction "2_2") (pintype "passive"))
      (node (ref "P17") (pin "1") (pinfunction "V_1") (pintype "passive"))
      (node (ref "P18") (pin "1") (pinfunction "V_1") (pintype "passive"))
      (node (ref "P19") (pin "2") (pinfunction "2_2") (pintype "passive"))
      (node (ref "P2") (pin "2") (pinfunction "2_2") (pintype "passive"))
      (node (ref "P20") (pin "2") (pinfunction "2_2") (pintype "passive"))
      (node (ref "P21") (pin "2") (pinfunction "2_2") (pintype "passive"))
      (node (ref "P25") (pin "2") (pinfunction "2_2") (pintype "passive"))
      (node (ref "P26") (pin "2") (pinfunction "2_2") (pintype "passive"))
      (node (ref "P27") (pin "2") (pinfunction "2_2") (pintype "passive"))
      (node (ref "P28") (pin "2") (pinfunction "2_2") (pintype "passive"))
      (node (ref "P29") (pin "2") (pinfunction "2_2") (pintype "passive"))
      (node (ref "P3") (pin "2") (pinfunction "2_2") (pintype "passive"))
      (node (ref "P6") (pin "2") (pinfunction "2_2") (pintype "passive"))
      (node (ref "P7") (pin "2") (pinfunction "2_2") (pintype "passive"))
      (node (ref "P9") (pin "2") (pinfunction "2_2") (pintype "passive"))
      (node (ref "U18") (pin "9") (pinfunction "VBB_9") (pintype "passive"))
      (node (ref "U4") (pin "7") (pinfunction "VIN_7") (pintype "passive"))
    )
    (net (code "67") (name "GND") (class "Default")
      (node (ref "C1") (pin "2") (pinfunction "2_2") (pintype "passive"))
      (node (ref "C10") (pin "1") (pinfunction "1_1") (pintype "passive"))
      (node (ref "C11") (pin "2") (pinfunction "2_2") (pintype "passive"))
      (node (ref "C12") (pin "2") (pinfunction "2_2") (pintype "passive"))
      (node (ref "C13") (pin "1") (pinfunction "1_1") (pintype "passive"))
      (node (ref "C14") (pin "1") (pinfunction "1_1") (pintype "passive"))
      (node (ref "C15") (pin "1") (pinfunction "1_1") (pintype "passive"))
      (node (ref "C16") (pin "1") (pinfunction "1_1") (pintype "passive"))
      (node (ref "C17") (pin "2") (pinfunction "2_2") (pintype "passive"))
      (node (ref "C18") (pin "1") (pinfunction "1_1") (pintype "passive"))
      (node (ref "C19") (pin "1") (pinfunction "1_1") (pintype "passive"))
      (node (ref "C2") (pin "2") (pinfunction "2_2") (pintype "passive"))
      (node (ref "C20") (pin "2") (pinfunction "2_2") (pintype "passive"))
      (node (ref "C22") (pin "2") (pinfunction "2_2") (pintype "passive"))
      (node (ref "C23") (pin "2") (pinfunction "2_2") (pintype "passive"))
      (node (ref "C24") (pin "1") (pinfunction "1_1") (pintype "passive"))
      (node (ref "C25") (pin "1") (pinfunction "1_1") (pintype "passive"))
      (node (ref "C26") (pin "1") (pinfunction "1_1") (pintype "passive"))
      (node (ref "C27") (pin "1") (pinfunction "1_1") (pintype "passive"))
      (node (ref "C28") (pin "2") (pinfunction "2_2") (pintype "passive"))
      (node (ref "C29") (pin "2") (pinfunction "2_2") (pintype "passive"))
      (node (ref "C3") (pin "1") (pinfunction "1_1") (pintype "passive"))
      (node (ref "C30") (pin "2") (pinfunction "2_2") (pintype "passive"))
      (node (ref "C31") (pin "1") (pinfunction "1_1") (pintype "passive"))
      (node (ref "C32") (pin "1") (pinfunction "1_1") (pintype "passive"))
      (node (ref "C33") (pin "1") (pinfunction "1_1") (pintype "passive"))
      (node (ref "C34") (pin "1") (pinfunction "1_1") (pintype "passive"))
      (node (ref "C35") (pin "2") (pinfunction "2_2") (pintype "passive"))
      (node (ref "C4") (pin "1") (pinfunction "1_1") (pintype "passive"))
      (node (ref "C5") (pin "1") (pinfunction "1_1") (pintype "passive"))
      (node (ref "C6") (pin "1") (pinfunction "1_1") (pintype "passive"))
      (node (ref "C7") (pin "1") (pinfunction "1_1") (pintype "passive"))
      (node (ref "C8") (pin "1") (pinfunction "1_1") (pintype "passive"))
      (node (ref "C9") (pin "1") (pinfunction "1_1") (pintype "passive"))
      (node (ref "D1") (pin "2") (pinfunction "K_2") (pintype "passive"))
      (node (ref "D2") (pin "1") (pinfunction "A_1") (pintype "passive"))
      (node (ref "D3") (pin "1") (pinfunction "A_1") (pintype "passive"))
      (node (ref "D4") (pin "1") (pinfunction "A_1") (pintype "passive"))
      (node (ref "D5") (pin "2") (pinfunction "K_2") (pintype "passive"))
      (node (ref "D6") (pin "1") (pinfunction "A_1") (pintype "passive"))
      (node (ref "D7") (pin "1") (pinfunction "A_1") (pintype "passive"))
      (node (ref "D8") (pin "1") (pinfunction "A_1") (pintype "passive"))
      (node (ref "D9") (pin "1") (pinfunction "A_1") (pintype "passive"))
      (node (ref "J1") (pin "5") (pinfunction "VSS_5") (pintype "passive"))
      (node (ref "J2") (pin "2") (pinfunction "2_2") (pintype "passive"))
      (node (ref "P11") (pin "1") (pinfunction "1_1") (pintype "passive"))
      (node (ref "P12") (pin "1") (pinfunction "1_1") (pintype "passive"))
      (node (ref "P13") (pin "2") (pinfunction "G_2") (pintype "passive"))
      (node (ref "P14") (pin "2") (pinfunction "G_2") (pintype "passive"))
      (node (ref "P15") (pin "1") (pinfunction "1_1") (pintype "passive"))
      (node (ref "P16") (pin "2") (pinfunction "2_2") (pintype "passive"))
      (node (ref "P16") (pin "4") (pinfunction "4_4") (pintype "passive"))
      (node (ref "P17") (pin "2") (pinfunction "G_2") (pintype "passive"))
      (node (ref "P18") (pin "2") (pinfunction "G_2") (pintype "passive"))
      (node (ref "P2") (pin "1") (pinfunction "1_1") (pintype "passive"))
      (node (ref "P22") (pin "3") (pinfunction "3_3") (pintype "passive"))
      (node (ref "P23") (pin "4") (pinfunction "4_4") (pintype "passive"))
      (node (ref "P3") (pin "1") (pinfunction "1_1") (pintype "passive"))
      (node (ref "P30") (pin "2") (pinfunction "2_2") (pintype "passive"))
      (node (ref "P31") (pin "2") (pinfunction "2_2") (pintype "passive"))
      (node (ref "P32") (pin "2") (pinfunction "2_2") (pintype "passive"))
      (node (ref "P33") (pin "2") (pinfunction "2_2") (pintype "passive"))
      (node (ref "P34") (pin "3") (pinfunction "3_3") (pintype "passive"))
      (node (ref "P36") (pin "1") (pinfunction "1_1") (pintype "passive"))
      (node (ref "P38") (pin "2") (pinfunction "2_2") (pintype "passive"))
      (node (ref "P38") (pin "4") (pinfunction "4_4") (pintype "passive"))
      (node (ref "P39") (pin "1") (pinfunction "1_1") (pintype "passive"))
      (node (ref "P5") (pin "2") (pinfunction "2_2") (pintype "passive"))
      (node (ref "P6") (pin "1") (pinfunction "1_1") (pintype "passive"))
      (node (ref "P7") (pin "1") (pinfunction "1_1") (pintype "passive"))
      (node (ref "P9") (pin "1") (pinfunction "1_1") (pintype "passive"))
      (node (ref "R3") (pin "2") (pinfunction "2_2") (pintype "passive"))
      (node (ref "U1") (pin "2") (pinfunction "GND_2") (pintype "passive"))
      (node (ref "U1") (pin "8") (pinfunction "~{CS}_8") (pintype "passive"))
      (node (ref "U10") (pin "2") (pinfunction "b_2") (pintype "passive"))
      (node (ref "U11") (pin "2") (pinfunction "b_2") (pintype "passive"))
      (node (ref "U12") (pin "2") (pinfunction "b_2") (pintype "passive"))
      (node (ref "U13") (pin "2") (pinfunction "b_2") (pintype "passive"))
      (node (ref "U14") (pin "2") (pinfunction "b_2") (pintype "passive"))
      (node (ref "U15") (pin "2") (pinfunction "b_2") (pintype "passive"))
      (node (ref "U16") (pin "2") (pinfunction "b_2") (pintype "passive"))
      (node (ref "U17") (pin "2") (pinfunction "b_2") (pintype "passive"))
      (node (ref "U18") (pin "0") (pinfunction "GNDPAD_0") (pintype "passive"))
      (node (ref "U18") (pin "13") (pinfunction "GND_13") (pintype "passive"))
      (node (ref "U18") (pin "2") (pinfunction "MODE_2") (pintype "passive"))
      (node (ref "U18") (pin "4") (pinfunction "GND_4") (pintype "passive"))
      (node (ref "U18") (pin "8") (pinfunction "SENSE_8") (pintype "passive"))
      (node (ref "U2") (pin "2") (pinfunction "GND_2") (pintype "passive"))
      (node (ref "U2") (pin "8") (pinfunction "~{CS}_8") (pintype "passive"))
      (node (ref "U4") (pin "6") (pinfunction "GND_6") (pintype "passive"))
      (node (ref "U5") (pin "12") (pinfunction "VSSA_12") (pintype "power_in"))
      (node (ref "U5") (pin "18") (pinfunction "VSS_18") (pintype "power_in"))
      (node (ref "U5") (pin "28") (pinfunction "PB2-BOOT1(PB2)_28") (pintype "bidirectional"))
      (node (ref "U5") (pin "60") (pinfunction "BOOT0_60") (pintype "input"))
      (node (ref "U5") (pin "63") (pinfunction "VSS_63") (pintype "power_in"))
      (node (ref "U6") (pin "1") (pinfunction "GND_1") (pintype "passive"))
      (node (ref "U8") (pin "2") (pinfunction "b_2") (pintype "passive"))
      (node (ref "U9") (pin "2") (pinfunction "b_2") (pintype "passive"))
    )
    (net (code "68") (name "Net-(D1-A)") (class "Default")
      (node (ref "D1") (pin "1") (pinfunction "A_1") (pintype "passive"))
      (node (ref "R5") (pin "1") (pinfunction "1_1") (pintype "passive"))
    )
    (net (code "69") (name "Net-(D2-K)") (class "Default")
      (node (ref "C21") (pin "1") (pinfunction "1_1") (pintype "passive"))
      (node (ref "D2") (pin "2") (pinfunction "K_2") (pintype "passive"))
      (node (ref "L1") (pin "1") (pinfunction "1_1") (pintype "passive"))
      (node (ref "U4") (pin "8") (pinfunction "PH_8") (pintype "passive"))
    )
    (net (code "70") (name "Net-(D5-A)") (class "Default")
      (node (ref "D5") (pin "1") (pinfunction "A_1") (pintype "passive"))
      (node (ref "R10") (pin "1") (pinfunction "1_1") (pintype "passive"))
    )
    (net (code "71") (name "Net-(D10-A)") (class "Default")
      (node (ref "D10") (pin "1") (pinfunction "A_1") (pintype "passive"))
      (node (ref "R16") (pin "2") (pinfunction "2_2") (pintype "passive"))
    )
    (net (code "72") (name "Net-(D10-K)") (class "Default")
      (node (ref "D10") (pin "2") (pinfunction "K_2") (pintype "passive"))
      (node (ref "U10") (pin "3") (pinfunction "c_3") (pintype "passive"))
      (node (ref "U7") (pin "2") (pinfunction "B_2") (pintype "passive"))
    )
    (net (code "73") (name "Net-(P36-Pad3)") (class "Default")
      (node (ref "P36") (pin "3") (pinfunction "3_3") (pintype "passive"))
      (node (ref "R12") (pin "2") (pinfunction "2_2") (pintype "passive"))
    )
    (net (code "74") (name "Net-(U3-OSC1)") (class "Default")
      (node (ref "C17") (pin "1") (pinfunction "1_1") (pintype "passive"))
      (node (ref "U3") (pin "1") (pinfunction "OSC1_1") (pintype "passive"))
      (node (ref "U5") (pin "5") (pinfunction "PH0-OSC_IN(PH0)_5") (pintype "bidirectional"))
    )
    (net (code "75") (name "Net-(U3-OSC2)") (class "Default")
      (node (ref "C20") (pin "1") (pinfunction "1_1") (pintype "passive"))
      (node (ref "U3") (pin "2") (pinfunction "OSC2_2") (pintype "passive"))
      (node (ref "U5") (pin "6") (pinfunction "PH1-OSC_OUT(PH1)_6") (pintype "bidirectional"))
    )
    (net (code "76") (name "Net-(U4-BOOT)") (class "Default")
      (node (ref "C21") (pin "2") (pinfunction "2_2") (pintype "passive"))
      (node (ref "U4") (pin "1") (pinfunction "BOOT_1") (pintype "passive"))
    )
    (net (code "77") (name "Net-(U4-VSENSE)") (class "Default")
      (node (ref "R3") (pin "1") (pinfunction "1_1") (pintype "passive"))
      (node (ref "R4") (pin "2") (pinfunction "2_2") (pintype "passive"))
      (node (ref "U4") (pin "4") (pinfunction "VSENSE_4") (pintype "passive"))
    )
    (net (code "78") (name "Net-(U5A-NRST)") (class "Default")
      (node (ref "C28") (pin "1") (pinfunction "1_1") (pintype "passive"))
      (node (ref "J2") (pin "1") (pinfunction "1_1") (pintype "passive"))
      (node (ref "R6") (pin "1") (pinfunction "1_1") (pintype "passive"))
      (node (ref "U5") (pin "7") (pinfunction "NRST_7") (pintype "bidirectional"))
    )
    (net (code "79") (name "Net-(U5A-VCAP_1)") (class "Default")
      (node (ref "C29") (pin "1") (pinfunction "1_1") (pintype "passive"))
      (node (ref "U5") (pin "31") (pinfunction "VCAP_1_31") (pintype "power_in"))
    )
    (net (code "80") (name "Net-(U5A-VCAP_2)") (class "Default")
      (node (ref "C30") (pin "1") (pinfunction "1_1") (pintype "passive"))
      (node (ref "U5") (pin "47") (pinfunction "VCAP_2_47") (pintype "power_in"))
    )
    (net (code "81") (name "Net-(U10-e)") (class "Default")
      (node (ref "R9") (pin "1") (pinfunction "1_1") (pintype "passive"))
      (node (ref "U10") (pin "1") (pinfunction "e_1") (pintype "passive"))
    )
    (net (code "82") (name "Net-(U11-c)") (class "Default")
      (node (ref "P24") (pin "1") (pinfunction "1_1") (pintype "passive"))
      (node (ref "U11") (pin "3") (pinfunction "c_3") (pintype "passive"))
    )
    (net (code "83") (name "Net-(U16-c)") (class "Default")
      (node (ref "P37") (pin "1") (pinfunction "1_1") (pintype "passive"))
      (node (ref "U16") (pin "3") (pinfunction "c_3") (pintype "passive"))
    )
    (net (code "84") (name "Net-(U17-e)") (class "Default")
      (node (ref "R12") (pin "1") (pinfunction "1_1") (pintype "passive"))
      (node (ref "U17") (pin "1") (pinfunction "e_1") (pintype "passive"))
    )
    (net (code "85") (name "Net-(U18-CP1)") (class "Default")
      (node (ref "C37") (pin "2") (pinfunction "2_2") (pintype "passive"))
      (node (ref "U18") (pin "11") (pinfunction "CP1_11") (pintype "passive"))
    )
    (net (code "86") (name "Net-(U18-CP2)") (class "Default")
      (node (ref "C37") (pin "1") (pinfunction "1_1") (pintype "passive"))
      (node (ref "U18") (pin "12") (pinfunction "CP2_12") (pintype "passive"))
    )
    (net (code "87") (name "Net-(U18-OUT+)") (class "Default")
      (node (ref "P40") (pin "2") (pinfunction "2_2") (pintype "passive"))
      (node (ref "U18") (pin "7") (pinfunction "OUT+_7") (pintype "passive"))
    )
    (net (code "88") (name "Net-(U18-OUT-)") (class "Default")
      (node (ref "P40") (pin "1") (pinfunction "1_1") (pintype "passive"))
      (node (ref "U18") (pin "10") (pinfunction "OUT-_10") (pintype "passive"))
    )
    (net (code "89") (name "Net-(U18-VCP)") (class "Default")
      (node (ref "C36") (pin "1") (pinfunction "1_1") (pintype "passive"))
      (node (ref "U18") (pin "14") (pinfunction "VCP_14") (pintype "passive"))
    )
    (net (code "90") (name "Net-(U18-VREG)") (class "Default")
      (node (ref "C35") (pin "1") (pinfunction "1_1") (pintype "passive"))
      (node (ref "U18") (pin "15") (pinfunction "VREG_15") (pintype "passive"))
    )
    (net (code "91") (name "Net-(U18-nFAULT)") (class "Default")
      (node (ref "R13") (pin "1") (pinfunction "1_1") (pintype "passive"))
      (node (ref "U18") (pin "1") (pinfunction "nFAULT_1") (pintype "passive"))
    )
    (net (code "92") (name "unconnected-(J1-ID-Pad4)") (class "Default")
      (node (ref "J1") (pin "4") (pinfunction "ID_4") (pintype "passive+no_connect"))
    )
    (net (code "93") (name "unconnected-(P5-Pad5)") (class "Default")
      (node (ref "P5") (pin "5") (pinfunction "5_5") (pintype "passive+no_connect"))
    )
    (net (code "94") (name "unconnected-(P5-Pad6)") (class "Default")
      (node (ref "P5") (pin "6") (pinfunction "6_6") (pintype "passive+no_connect"))
    )
    (net (code "95") (name "unconnected-(P5-Pad8)") (class "Default")
      (node (ref "P5") (pin "8") (pinfunction "8_8") (pintype "passive+no_connect"))
    )
    (net (code "96") (name "unconnected-(U1-VREF-Pad5)") (class "Default")
      (node (ref "U1") (pin "5") (pinfunction "VREF_5") (pintype "passive+no_connect"))
    )
    (net (code "97") (name "unconnected-(U2-VREF-Pad5)") (class "Default")
      (node (ref "U2") (pin "5") (pinfunction "VREF_5") (pintype "passive+no_connect"))
    )
    (net (code "98") (name "unconnected-(U4-ENA-Pad5)") (class "Default")
      (node (ref "U4") (pin "5") (pinfunction "ENA_5") (pintype "passive+no_connect"))
    )
    (net (code "99") (name "unconnected-(U4-NC-Pad2)") (class "Default")
      (node (ref "U4") (pin "2") (pinfunction "NC_2") (pintype "passive+no_connect"))
    )
    (net (code "100") (name "unconnected-(U4-NC-Pad3)") (class "Default")
      (node (ref "U4") (pin "3") (pinfunction "NC_3") (pintype "passive+no_connect"))
    )
    (net (code "101") (name "unconnected-(U5A-PA12-Pad45)") (class "Default")
      (node (ref "U5") (pin "45") (pinfunction "PA12_45") (pintype "bidirectional"))
    )
    (net (code "102") (name "unconnected-(U5A-PB15-Pad36)") (class "Default")
      (node (ref "U5") (pin "36") (pinfunction "PB15_36") (pintype "bidirectional"))
    )
    (net (code "103") (name "unconnected-(U5A-PC10-Pad51)") (class "Default")
      (node (ref "U5") (pin "51") (pinfunction "PC10_51") (pintype "bidirectional"))
    )
    (net (code "104") (name "unconnected-(U18-NC-Pad16)") (class "Default")
      (node (ref "U18") (pin "16") (pinfunction "NC_16") (pintype "passive+no_connect"))
    )
  )
)
